# VCO3340_v2_1.net
KiCad netlist of a schematic drawn in EAGLE
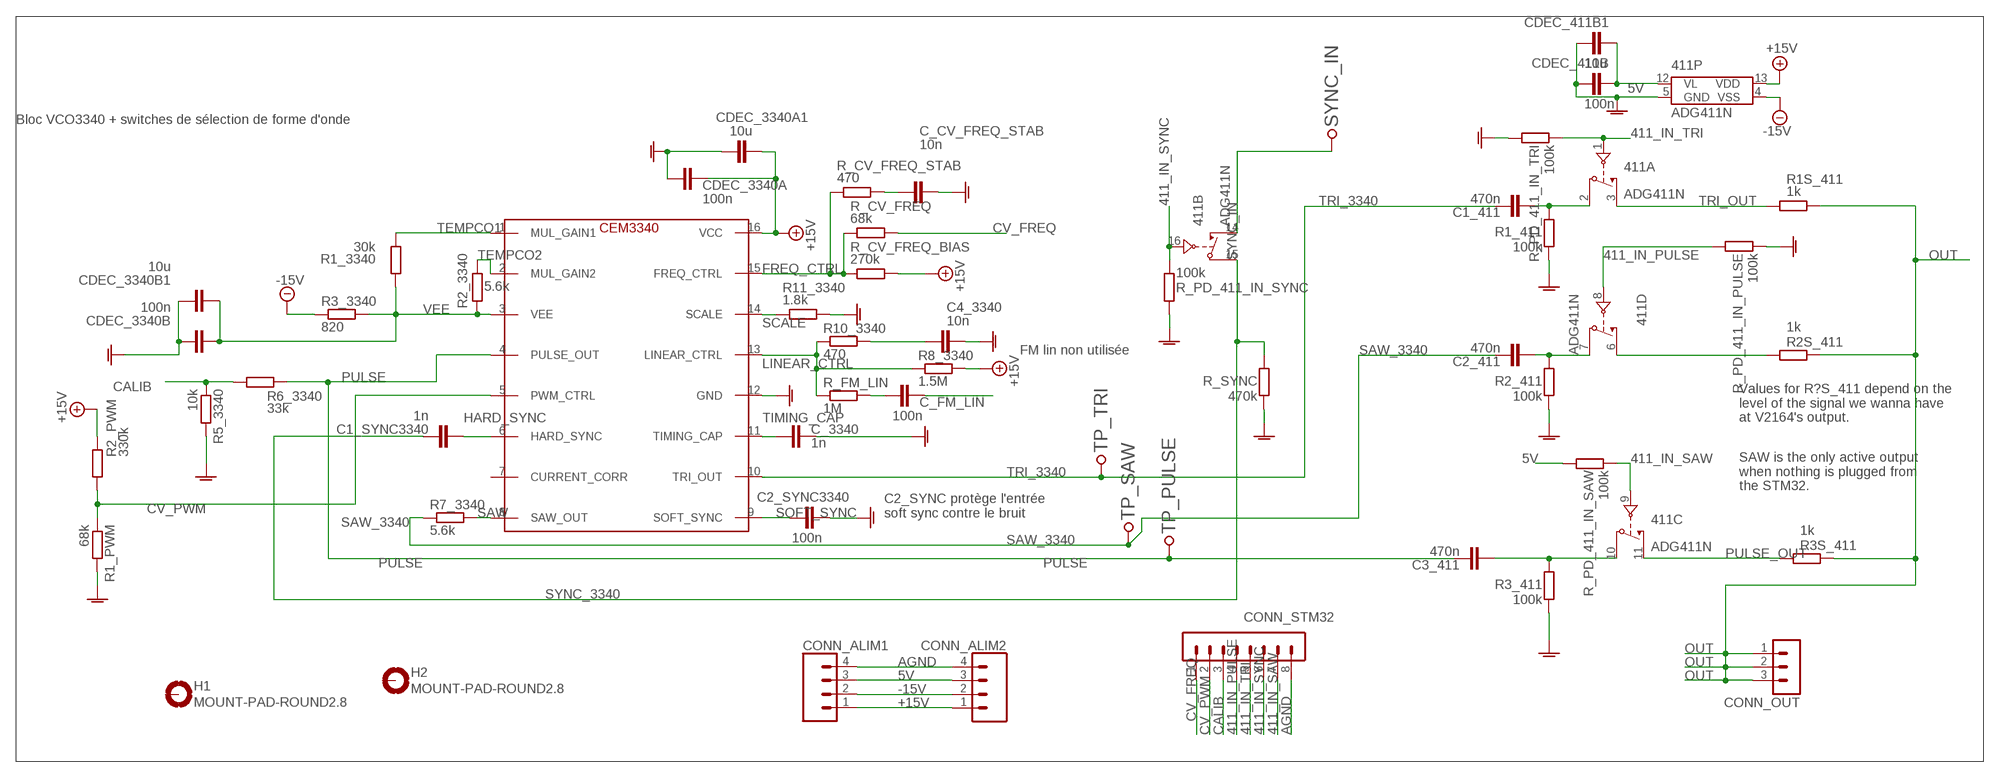
[diagram p0: schematic, sheet 1]

(export (version "E")
  (design (tool "Eeschema 10.0.6"))
  (components
    (comp (ref "411")
      (value "ADG411N")
      (footprint "eagle-import:DIL16")
      (fields (field (name "MF") "ALTERA CORPORATION") (field (name "MPN") "ADG411BN"))
      (libsource (lib "eagle-import") (part "ADG411N"))
    )
    (comp (ref "C1_411")
      (value "470n")
      (footprint "eagle-import:C050-030X075")
      (libsource (lib "eagle-import") (part "C-EU050-030X075"))
    )
    (comp (ref "C1_SYNC3340")
      (value "1n")
      (footprint "eagle-import:C075-032X103")
      (libsource (lib "eagle-import") (part "C-EU075-032X103"))
    )
    (comp (ref "C2_411")
      (value "470n")
      (footprint "eagle-import:C075-032X103")
      (libsource (lib "eagle-import") (part "C-EU075-032X103"))
    )
    (comp (ref "C2_SYNC3340")
      (value "100n")
      (footprint "eagle-import:C075-032X103")
      (libsource (lib "eagle-import") (part "C-EU075-032X103"))
    )
    (comp (ref "C3_411")
      (value "470n")
      (footprint "eagle-import:C102-043X133")
      (libsource (lib "eagle-import") (part "C-EU102-043X133"))
    )
    (comp (ref "C4_3340")
      (value "10n")
      (footprint "eagle-import:C050-025X075")
      (libsource (lib "eagle-import") (part "C-EU050-025X075"))
    )
    (comp (ref "CDEC_411B")
      (value "100n")
      (footprint "eagle-import:C050-025X075")
      (libsource (lib "eagle-import") (part "C-EU050-025X075"))
    )
    (comp (ref "CDEC_411B1")
      (value "10u")
      (footprint "eagle-import:C050-025X075")
      (libsource (lib "eagle-import") (part "C-EU050-025X075"))
    )
    (comp (ref "CDEC_3340A")
      (value "100n")
      (footprint "eagle-import:C050-025X075")
      (libsource (lib "eagle-import") (part "C-EU050-025X075"))
    )
    (comp (ref "CDEC_3340A1")
      (value "10u")
      (footprint "eagle-import:C050-025X075")
      (libsource (lib "eagle-import") (part "C-EU050-025X075"))
    )
    (comp (ref "CDEC_3340B")
      (value "100n")
      (footprint "eagle-import:C050-025X075")
      (libsource (lib "eagle-import") (part "C-EU050-025X075"))
    )
    (comp (ref "CDEC_3340B1")
      (value "10u")
      (footprint "eagle-import:C050-025X075")
      (libsource (lib "eagle-import") (part "C-EU050-025X075"))
    )
    (comp (ref "CEM3340")
      (value "CEM3340")
      (footprint "eagle-import:DIL16")
      (libsource (lib "eagle-import") (part "CEM3340"))
    )
    (comp (ref "CONN_ALIM1")
      (value "CONN_04")
      (footprint "eagle-import:1X04")
      (libsource (lib "eagle-import") (part "CONN_04"))
    )
    (comp (ref "CONN_ALIM2")
      (value "CONN_04")
      (footprint "eagle-import:1X04")
      (libsource (lib "eagle-import") (part "CONN_04"))
    )
    (comp (ref "CONN_OUT")
      (value "MA03-1")
      (footprint "eagle-import:MA03-1")
      (libsource (lib "eagle-import") (part "MA03-1"))
    )
    (comp (ref "CONN_STM32")
      (value "MA08-1")
      (footprint "eagle-import:MA08-1")
      (libsource (lib "eagle-import") (part "MA08-1"))
    )
    (comp (ref "C_3340")
      (value "1n")
      (footprint "eagle-import:C050-025X075")
      (libsource (lib "eagle-import") (part "C-EU050-025X075"))
    )
    (comp (ref "C_CV_FREQ_STAB")
      (value "10n")
      (footprint "eagle-import:C075-032X103")
      (libsource (lib "eagle-import") (part "C-EU075-032X103"))
    )
    (comp (ref "C_FM_LIN")
      (value "100n")
      (footprint "eagle-import:C050-025X075")
      (libsource (lib "eagle-import") (part "C-EU050-025X075"))
    )
    (comp (ref "H1")
      (value "MOUNT-PAD-ROUND2.8")
      (footprint "eagle-import:2,8-PAD")
      (libsource (lib "eagle-import") (part "MOUNT-PAD-ROUND2.8"))
    )
    (comp (ref "H2")
      (value "MOUNT-PAD-ROUND2.8")
      (footprint "eagle-import:2,8-PAD")
      (libsource (lib "eagle-import") (part "MOUNT-PAD-ROUND2.8"))
    )
    (comp (ref "R1S_411")
      (value "1k")
      (footprint "eagle-import:0204_7")
      (libsource (lib "eagle-import") (part "R-EU_0204/7"))
    )
    (comp (ref "R1_411")
      (value "100k")
      (footprint "eagle-import:0207_10")
      (libsource (lib "eagle-import") (part "R-EU_0207/10"))
    )
    (comp (ref "R1_3340")
      (value "30k")
      (footprint "eagle-import:0204_7")
      (libsource (lib "eagle-import") (part "R-EU_0204/7"))
    )
    (comp (ref "R1_PWM")
      (value "68k")
      (footprint "eagle-import:0207_12")
      (libsource (lib "eagle-import") (part "R-EU_0207/12"))
    )
    (comp (ref "R2S_411")
      (value "1k")
      (footprint "eagle-import:0207_10")
      (libsource (lib "eagle-import") (part "R-EU_0207/10"))
    )
    (comp (ref "R2_411")
      (value "100k")
      (footprint "eagle-import:0207_10")
      (libsource (lib "eagle-import") (part "R-EU_0207/10"))
    )
    (comp (ref "R2_3340")
      (value "5.6k")
      (footprint "eagle-import:0204_7")
      (libsource (lib "eagle-import") (part "R-EU_0204/7"))
    )
    (comp (ref "R2_PWM")
      (value "330k")
      (footprint "eagle-import:0204_7")
      (libsource (lib "eagle-import") (part "R-EU_0204/7"))
    )
    (comp (ref "R3S_411")
      (value "1k")
      (footprint "eagle-import:0204_7")
      (libsource (lib "eagle-import") (part "R-EU_0204/7"))
    )
    (comp (ref "R3_411")
      (value "100k")
      (footprint "eagle-import:0204_7")
      (libsource (lib "eagle-import") (part "R-EU_0204/7"))
    )
    (comp (ref "R3_3340")
      (value "820")
      (footprint "eagle-import:0204_7")
      (libsource (lib "eagle-import") (part "R-EU_0204/7"))
    )
    (comp (ref "R5_3340")
      (value "10k")
      (footprint "eagle-import:0204_7")
      (libsource (lib "eagle-import") (part "R-EU_0204/7"))
    )
    (comp (ref "R6_3340")
      (value "33k")
      (footprint "eagle-import:0204_7")
      (libsource (lib "eagle-import") (part "R-EU_0204/7"))
    )
    (comp (ref "R7_3340")
      (value "5.6k")
      (footprint "eagle-import:0207_10")
      (libsource (lib "eagle-import") (part "R-EU_0207/10"))
    )
    (comp (ref "R8_3340")
      (value "1.5M")
      (footprint "eagle-import:0204_7")
      (libsource (lib "eagle-import") (part "R-EU_0204/7"))
    )
    (comp (ref "R10_3340")
      (value "470")
      (footprint "eagle-import:0204_7")
      (libsource (lib "eagle-import") (part "R-EU_0204/7"))
    )
    (comp (ref "R11_3340")
      (value "1.8k")
      (footprint "eagle-import:0204_7")
      (libsource (lib "eagle-import") (part "R-EU_0204/7"))
    )
    (comp (ref "R_CV_FREQ")
      (value "68k")
      (footprint "eagle-import:0204_7")
      (libsource (lib "eagle-import") (part "R-EU_0204/7"))
    )
    (comp (ref "R_CV_FREQ_BIAS")
      (value "270k")
      (footprint "eagle-import:0204_7")
      (libsource (lib "eagle-import") (part "R-EU_0204/7"))
    )
    (comp (ref "R_CV_FREQ_STAB")
      (value "470")
      (footprint "eagle-import:0204_7")
      (libsource (lib "eagle-import") (part "R-EU_0204/7"))
    )
    (comp (ref "R_FM_LIN")
      (value "1M")
      (footprint "eagle-import:0204_7")
      (libsource (lib "eagle-import") (part "R-EU_0204/7"))
    )
    (comp (ref "R_PD_411_IN_PULSE")
      (value "100k")
      (footprint "eagle-import:0207_10")
      (libsource (lib "eagle-import") (part "R-EU_0207/10"))
    )
    (comp (ref "R_PD_411_IN_SAW")
      (value "100k")
      (footprint "eagle-import:0207_10")
      (libsource (lib "eagle-import") (part "R-EU_0207/10"))
    )
    (comp (ref "R_PD_411_IN_SYNC")
      (value "100k")
      (footprint "eagle-import:0204_7")
      (libsource (lib "eagle-import") (part "R-EU_0204/7"))
    )
    (comp (ref "R_PD_411_IN_TRI")
      (value "100k")
      (footprint "eagle-import:0204_7")
      (libsource (lib "eagle-import") (part "R-EU_0204/7"))
    )
    (comp (ref "R_SYNC")
      (value "470k")
      (footprint "eagle-import:0204_7")
      (libsource (lib "eagle-import") (part "R-EU_0204/7"))
    )
    (comp (ref "SYNC_IN")
      (value "TESTPOINT")
      (footprint "eagle-import:TESTPOINT_63")
      (libsource (lib "eagle-import") (part "TESTPOINT"))
    )
    (comp (ref "TP_PULSE")
      (value "TESTPOINT")
      (footprint "eagle-import:TESTPOINT_63")
      (libsource (lib "eagle-import") (part "TESTPOINT"))
    )
    (comp (ref "TP_SAW")
      (value "TESTPOINT")
      (footprint "eagle-import:TESTPOINT_63")
      (libsource (lib "eagle-import") (part "TESTPOINT"))
    )
    (comp (ref "TP_TRI")
      (value "TESTPOINT")
      (footprint "eagle-import:TESTPOINT_63")
      (libsource (lib "eagle-import") (part "TESTPOINT"))
    )
  )
  (nets
    (net (code "1") (name "+15V") (class "Default")
      (node (ref "411") (pin "13") (pinfunction "VDD_13") (pintype "power_in"))
      (node (ref "CDEC_3340A") (pin "2") (pinfunction "2_2") (pintype "passive"))
      (node (ref "CDEC_3340A1") (pin "2") (pinfunction "2_2") (pintype "passive"))
      (node (ref "CEM3340") (pin "16") (pinfunction "VCC_16") (pintype "bidirectional"))
      (node (ref "CONN_ALIM1") (pin "1") (pinfunction "1_1") (pintype "passive"))
      (node (ref "CONN_ALIM2") (pin "1") (pinfunction "1_1") (pintype "passive"))
      (node (ref "R2_PWM") (pin "2") (pinfunction "2_2") (pintype "passive"))
      (node (ref "R8_3340") (pin "2") (pinfunction "2_2") (pintype "passive"))
      (node (ref "R_CV_FREQ_BIAS") (pin "2") (pinfunction "2_2") (pintype "passive"))
    )
    (net (code "2") (name "-15V") (class "Default")
      (node (ref "411") (pin "4") (pinfunction "VSS_4") (pintype "power_in"))
      (node (ref "CONN_ALIM1") (pin "2") (pinfunction "2_2") (pintype "passive"))
      (node (ref "CONN_ALIM2") (pin "2") (pinfunction "2_2") (pintype "passive"))
      (node (ref "R3_3340") (pin "1") (pinfunction "1_1") (pintype "passive"))
    )
    (net (code "3") (name "/5V") (class "Default")
      (node (ref "411") (pin "12") (pinfunction "VL_12") (pintype "power_in"))
      (node (ref "CDEC_411B") (pin "1") (pinfunction "1_1") (pintype "passive"))
      (node (ref "CDEC_411B1") (pin "1") (pinfunction "1_1") (pintype "passive"))
      (node (ref "CONN_ALIM1") (pin "3") (pinfunction "3_3") (pintype "passive"))
      (node (ref "CONN_ALIM2") (pin "3") (pinfunction "3_3") (pintype "passive"))
      (node (ref "R_PD_411_IN_SAW") (pin "2") (pinfunction "2_2") (pintype "passive"))
    )
    (net (code "4") (name "/411_IN_PULSE") (class "Default")
      (node (ref "411") (pin "8") (pinfunction "IN_8") (pintype "input"))
      (node (ref "CONN_STM32") (pin "4") (pinfunction "4_4") (pintype "passive"))
      (node (ref "R_PD_411_IN_PULSE") (pin "2") (pinfunction "2_2") (pintype "passive"))
    )
    (net (code "5") (name "/411_IN_SAW") (class "Default")
      (node (ref "411") (pin "9") (pinfunction "IN_9") (pintype "input"))
      (node (ref "CONN_STM32") (pin "7") (pinfunction "7_7") (pintype "passive"))
      (node (ref "R_PD_411_IN_SAW") (pin "1") (pinfunction "1_1") (pintype "passive"))
    )
    (net (code "6") (name "/411_IN_SYNC") (class "Default")
      (node (ref "411") (pin "16") (pinfunction "IN_16") (pintype "input"))
      (node (ref "CONN_STM32") (pin "6") (pinfunction "6_6") (pintype "passive"))
      (node (ref "R_PD_411_IN_SYNC") (pin "1") (pinfunction "1_1") (pintype "passive"))
    )
    (net (code "7") (name "/411_IN_TRI") (class "Default")
      (node (ref "411") (pin "1") (pinfunction "IN_1") (pintype "input"))
      (node (ref "CONN_STM32") (pin "5") (pinfunction "5_5") (pintype "passive"))
      (node (ref "R_PD_411_IN_TRI") (pin "1") (pinfunction "1_1") (pintype "passive"))
    )
    (net (code "8") (name "/CALIB") (class "Default")
      (node (ref "CONN_STM32") (pin "3") (pinfunction "3_3") (pintype "passive"))
      (node (ref "R5_3340") (pin "1") (pinfunction "1_1") (pintype "passive"))
      (node (ref "R6_3340") (pin "1") (pinfunction "1_1") (pintype "passive"))
    )
    (net (code "9") (name "/CV_FREQ") (class "Default")
      (node (ref "CONN_STM32") (pin "1") (pinfunction "1_1") (pintype "passive"))
      (node (ref "R_CV_FREQ") (pin "2") (pinfunction "2_2") (pintype "passive"))
    )
    (net (code "10") (name "/CV_PWM") (class "Default")
      (node (ref "CEM3340") (pin "5") (pinfunction "PWM_CTRL_5") (pintype "bidirectional"))
      (node (ref "CONN_STM32") (pin "2") (pinfunction "2_2") (pintype "passive"))
      (node (ref "R1_PWM") (pin "1") (pinfunction "1_1") (pintype "passive"))
      (node (ref "R2_PWM") (pin "1") (pinfunction "1_1") (pintype "passive"))
    )
    (net (code "11") (name "/FREQ_CTRL") (class "Default")
      (node (ref "CEM3340") (pin "15") (pinfunction "FREQ_CTRL_15") (pintype "bidirectional"))
      (node (ref "R_CV_FREQ") (pin "1") (pinfunction "1_1") (pintype "passive"))
      (node (ref "R_CV_FREQ_BIAS") (pin "1") (pinfunction "1_1") (pintype "passive"))
      (node (ref "R_CV_FREQ_STAB") (pin "1") (pinfunction "1_1") (pintype "passive"))
    )
    (net (code "12") (name "/HARD_SYNC") (class "Default")
      (node (ref "C1_SYNC3340") (pin "2") (pinfunction "2_2") (pintype "passive"))
      (node (ref "CEM3340") (pin "6") (pinfunction "HARD_SYNC_6") (pintype "bidirectional"))
    )
    (net (code "13") (name "/LINEAR_CTRL") (class "Default")
      (node (ref "CEM3340") (pin "13") (pinfunction "LINEAR_CTRL_13") (pintype "bidirectional"))
      (node (ref "R10_3340") (pin "1") (pinfunction "1_1") (pintype "passive"))
      (node (ref "R8_3340") (pin "1") (pinfunction "1_1") (pintype "passive"))
      (node (ref "R_FM_LIN") (pin "1") (pinfunction "1_1") (pintype "passive"))
    )
    (net (code "14") (name "/OUT") (class "Default")
      (node (ref "CONN_OUT") (pin "1") (pinfunction "1_1") (pintype "passive"))
      (node (ref "CONN_OUT") (pin "2") (pinfunction "2_2") (pintype "passive"))
      (node (ref "CONN_OUT") (pin "3") (pinfunction "3_3") (pintype "passive"))
      (node (ref "R1S_411") (pin "2") (pinfunction "2_2") (pintype "passive"))
      (node (ref "R2S_411") (pin "1") (pinfunction "1_1") (pintype "passive"))
      (node (ref "R3S_411") (pin "1") (pinfunction "1_1") (pintype "passive"))
    )
    (net (code "15") (name "/PULSE") (class "Default")
      (node (ref "C3_411") (pin "1") (pinfunction "1_1") (pintype "passive"))
      (node (ref "CEM3340") (pin "4") (pinfunction "PULSE_OUT_4") (pintype "bidirectional"))
      (node (ref "R6_3340") (pin "2") (pinfunction "2_2") (pintype "passive"))
      (node (ref "TP_PULSE") (pin "P$1") (pinfunction "P$1_P$1") (pintype "passive"))
    )
    (net (code "16") (name "/PULSE_OUT") (class "Default")
      (node (ref "411") (pin "11") (pinfunction "S_11") (pintype "passive"))
      (node (ref "R3S_411") (pin "2") (pinfunction "2_2") (pintype "passive"))
    )
    (net (code "17") (name "/SAW") (class "Default")
      (node (ref "CEM3340") (pin "8") (pinfunction "SAW_OUT_8") (pintype "bidirectional"))
      (node (ref "R7_3340") (pin "2") (pinfunction "2_2") (pintype "passive"))
    )
    (net (code "18") (name "/SAW_3340") (class "Default")
      (node (ref "C2_411") (pin "1") (pinfunction "1_1") (pintype "passive"))
      (node (ref "R7_3340") (pin "1") (pinfunction "1_1") (pintype "passive"))
      (node (ref "TP_SAW") (pin "P$1") (pinfunction "P$1_P$1") (pintype "passive"))
    )
    (net (code "19") (name "/SCALE") (class "Default")
      (node (ref "CEM3340") (pin "14") (pinfunction "SCALE_14") (pintype "bidirectional"))
      (node (ref "R11_3340") (pin "1") (pinfunction "1_1") (pintype "passive"))
    )
    (net (code "20") (name "/SOFT_SYNC") (class "Default")
      (node (ref "C2_SYNC3340") (pin "2") (pinfunction "2_2") (pintype "passive"))
      (node (ref "CEM3340") (pin "9") (pinfunction "SOFT_SYNC_9") (pintype "bidirectional"))
    )
    (net (code "21") (name "/SYNC_3340") (class "Default")
      (node (ref "411") (pin "15") (pinfunction "D_15") (pintype "passive"))
      (node (ref "C1_SYNC3340") (pin "1") (pinfunction "1_1") (pintype "passive"))
      (node (ref "R_SYNC") (pin "2") (pinfunction "2_2") (pintype "passive"))
    )
    (net (code "22") (name "/SYNC_IN") (class "Default")
      (node (ref "411") (pin "14") (pinfunction "S_14") (pintype "passive"))
      (node (ref "SYNC_IN") (pin "P$1") (pinfunction "P$1_P$1") (pintype "passive"))
    )
    (net (code "23") (name "/TEMPCO1") (class "Default")
      (node (ref "CEM3340") (pin "1") (pinfunction "MUL_GAIN1_1") (pintype "bidirectional"))
      (node (ref "R1_3340") (pin "1") (pinfunction "1_1") (pintype "passive"))
    )
    (net (code "24") (name "/TEMPCO2") (class "Default")
      (node (ref "CEM3340") (pin "2") (pinfunction "MUL_GAIN2_2") (pintype "bidirectional"))
      (node (ref "R2_3340") (pin "1") (pinfunction "1_1") (pintype "passive"))
    )
    (net (code "25") (name "/TIMING_CAP") (class "Default")
      (node (ref "CEM3340") (pin "11") (pinfunction "TIMING_CAP_11") (pintype "bidirectional"))
      (node (ref "C_3340") (pin "2") (pinfunction "2_2") (pintype "passive"))
    )
    (net (code "26") (name "/TRI_3340") (class "Default")
      (node (ref "C1_411") (pin "1") (pinfunction "1_1") (pintype "passive"))
      (node (ref "CEM3340") (pin "10") (pinfunction "TRI_OUT_10") (pintype "bidirectional"))
      (node (ref "TP_TRI") (pin "P$1") (pinfunction "P$1_P$1") (pintype "passive"))
    )
    (net (code "27") (name "/TRI_OUT") (class "Default")
      (node (ref "411") (pin "3") (pinfunction "S_3") (pintype "passive"))
      (node (ref "R1S_411") (pin "1") (pinfunction "1_1") (pintype "passive"))
    )
    (net (code "28") (name "/VEE") (class "Default")
      (node (ref "CDEC_3340B") (pin "2") (pinfunction "2_2") (pintype "passive"))
      (node (ref "CDEC_3340B1") (pin "2") (pinfunction "2_2") (pintype "passive"))
      (node (ref "CEM3340") (pin "3") (pinfunction "VEE_3") (pintype "bidirectional"))
      (node (ref "R1_3340") (pin "2") (pinfunction "2_2") (pintype "passive"))
      (node (ref "R2_3340") (pin "2") (pinfunction "2_2") (pintype "passive"))
      (node (ref "R3_3340") (pin "2") (pinfunction "2_2") (pintype "passive"))
    )
    (net (code "29") (name "AGND") (class "Default")
      (node (ref "411") (pin "5") (pinfunction "GND_5") (pintype "power_in"))
      (node (ref "C2_SYNC3340") (pin "1") (pinfunction "1_1") (pintype "passive"))
      (node (ref "C4_3340") (pin "2") (pinfunction "2_2") (pintype "passive"))
      (node (ref "CDEC_3340A") (pin "1") (pinfunction "1_1") (pintype "passive"))
      (node (ref "CDEC_3340A1") (pin "1") (pinfunction "1_1") (pintype "passive"))
      (node (ref "CDEC_3340B") (pin "1") (pinfunction "1_1") (pintype "passive"))
      (node (ref "CDEC_3340B1") (pin "1") (pinfunction "1_1") (pintype "passive"))
      (node (ref "CDEC_411B") (pin "2") (pinfunction "2_2") (pintype "passive"))
      (node (ref "CDEC_411B1") (pin "2") (pinfunction "2_2") (pintype "passive"))
      (node (ref "CEM3340") (pin "12") (pinfunction "GND_12") (pintype "bidirectional"))
      (node (ref "CONN_ALIM1") (pin "4") (pinfunction "4_4") (pintype "passive"))
      (node (ref "CONN_ALIM2") (pin "4") (pinfunction "4_4") (pintype "passive"))
      (node (ref "CONN_STM32") (pin "8") (pinfunction "8_8") (pintype "passive"))
      (node (ref "C_3340") (pin "1") (pinfunction "1_1") (pintype "passive"))
      (node (ref "C_CV_FREQ_STAB") (pin "1") (pinfunction "1_1") (pintype "passive"))
      (node (ref "R11_3340") (pin "2") (pinfunction "2_2") (pintype "passive"))
      (node (ref "R1_411") (pin "1") (pinfunction "1_1") (pintype "passive"))
      (node (ref "R1_PWM") (pin "2") (pinfunction "2_2") (pintype "passive"))
      (node (ref "R2_411") (pin "1") (pinfunction "1_1") (pintype "passive"))
      (node (ref "R3_411") (pin "1") (pinfunction "1_1") (pintype "passive"))
      (node (ref "R5_3340") (pin "2") (pinfunction "2_2") (pintype "passive"))
      (node (ref "R_PD_411_IN_PULSE") (pin "1") (pinfunction "1_1") (pintype "passive"))
      (node (ref "R_PD_411_IN_SYNC") (pin "2") (pinfunction "2_2") (pintype "passive"))
      (node (ref "R_PD_411_IN_TRI") (pin "2") (pinfunction "2_2") (pintype "passive"))
      (node (ref "R_SYNC") (pin "1") (pinfunction "1_1") (pintype "passive"))
    )
    (net (code "30") (name "Net-(411A-D)") (class "Default")
      (node (ref "411") (pin "2") (pinfunction "D_2") (pintype "passive"))
      (node (ref "C1_411") (pin "2") (pinfunction "2_2") (pintype "passive"))
      (node (ref "R1_411") (pin "2") (pinfunction "2_2") (pintype "passive"))
    )
    (net (code "31") (name "Net-(411C-D)") (class "Default")
      (node (ref "411") (pin "10") (pinfunction "D_10") (pintype "passive"))
      (node (ref "C3_411") (pin "2") (pinfunction "2_2") (pintype "passive"))
      (node (ref "R3_411") (pin "2") (pinfunction "2_2") (pintype "passive"))
    )
    (net (code "32") (name "Net-(411D-D)") (class "Default")
      (node (ref "411") (pin "7") (pinfunction "D_7") (pintype "passive"))
      (node (ref "C2_411") (pin "2") (pinfunction "2_2") (pintype "passive"))
      (node (ref "R2_411") (pin "2") (pinfunction "2_2") (pintype "passive"))
    )
    (net (code "33") (name "Net-(411D-S)") (class "Default")
      (node (ref "411") (pin "6") (pinfunction "S_6") (pintype "passive"))
      (node (ref "R2S_411") (pin "2") (pinfunction "2_2") (pintype "passive"))
    )
    (net (code "34") (name "Net-(C4_3340-Pad1)") (class "Default")
      (node (ref "C4_3340") (pin "1") (pinfunction "1_1") (pintype "passive"))
      (node (ref "R10_3340") (pin "2") (pinfunction "2_2") (pintype "passive"))
    )
    (net (code "35") (name "Net-(C_CV_FREQ_STAB-Pad2)") (class "Default")
      (node (ref "C_CV_FREQ_STAB") (pin "2") (pinfunction "2_2") (pintype "passive"))
      (node (ref "R_CV_FREQ_STAB") (pin "2") (pinfunction "2_2") (pintype "passive"))
    )
    (net (code "36") (name "Net-(C_FM_LIN-Pad1)") (class "Default")
      (node (ref "C_FM_LIN") (pin "1") (pinfunction "1_1") (pintype "passive"))
      (node (ref "R_FM_LIN") (pin "2") (pinfunction "2_2") (pintype "passive"))
    )
    (net (code "37") (name "unconnected-(CEM3340-CURRENT_CORR-Pad7)") (class "Default")
      (node (ref "CEM3340") (pin "7") (pinfunction "CURRENT_CORR_7") (pintype "bidirectional"))
    )
    (net (code "38") (name "unconnected-(C_FM_LIN-Pad2)") (class "Default")
      (node (ref "C_FM_LIN") (pin "2") (pinfunction "2_2") (pintype "passive"))
    )
    (net (code "39") (name "unconnected-(H1-MOUNT-PadB2,8)") (class "Default")
      (node (ref "H1") (pin "B2,8") (pinfunction "MOUNT_B2,8") (pintype "passive"))
    )
    (net (code "40") (name "unconnected-(H2-MOUNT-PadB2,8)") (class "Default")
      (node (ref "H2") (pin "B2,8") (pinfunction "MOUNT_B2,8") (pintype "passive"))
    )
  )
)
